# Rx_micro.net
KiCad netlist of a schematic drawn in Altium Designer
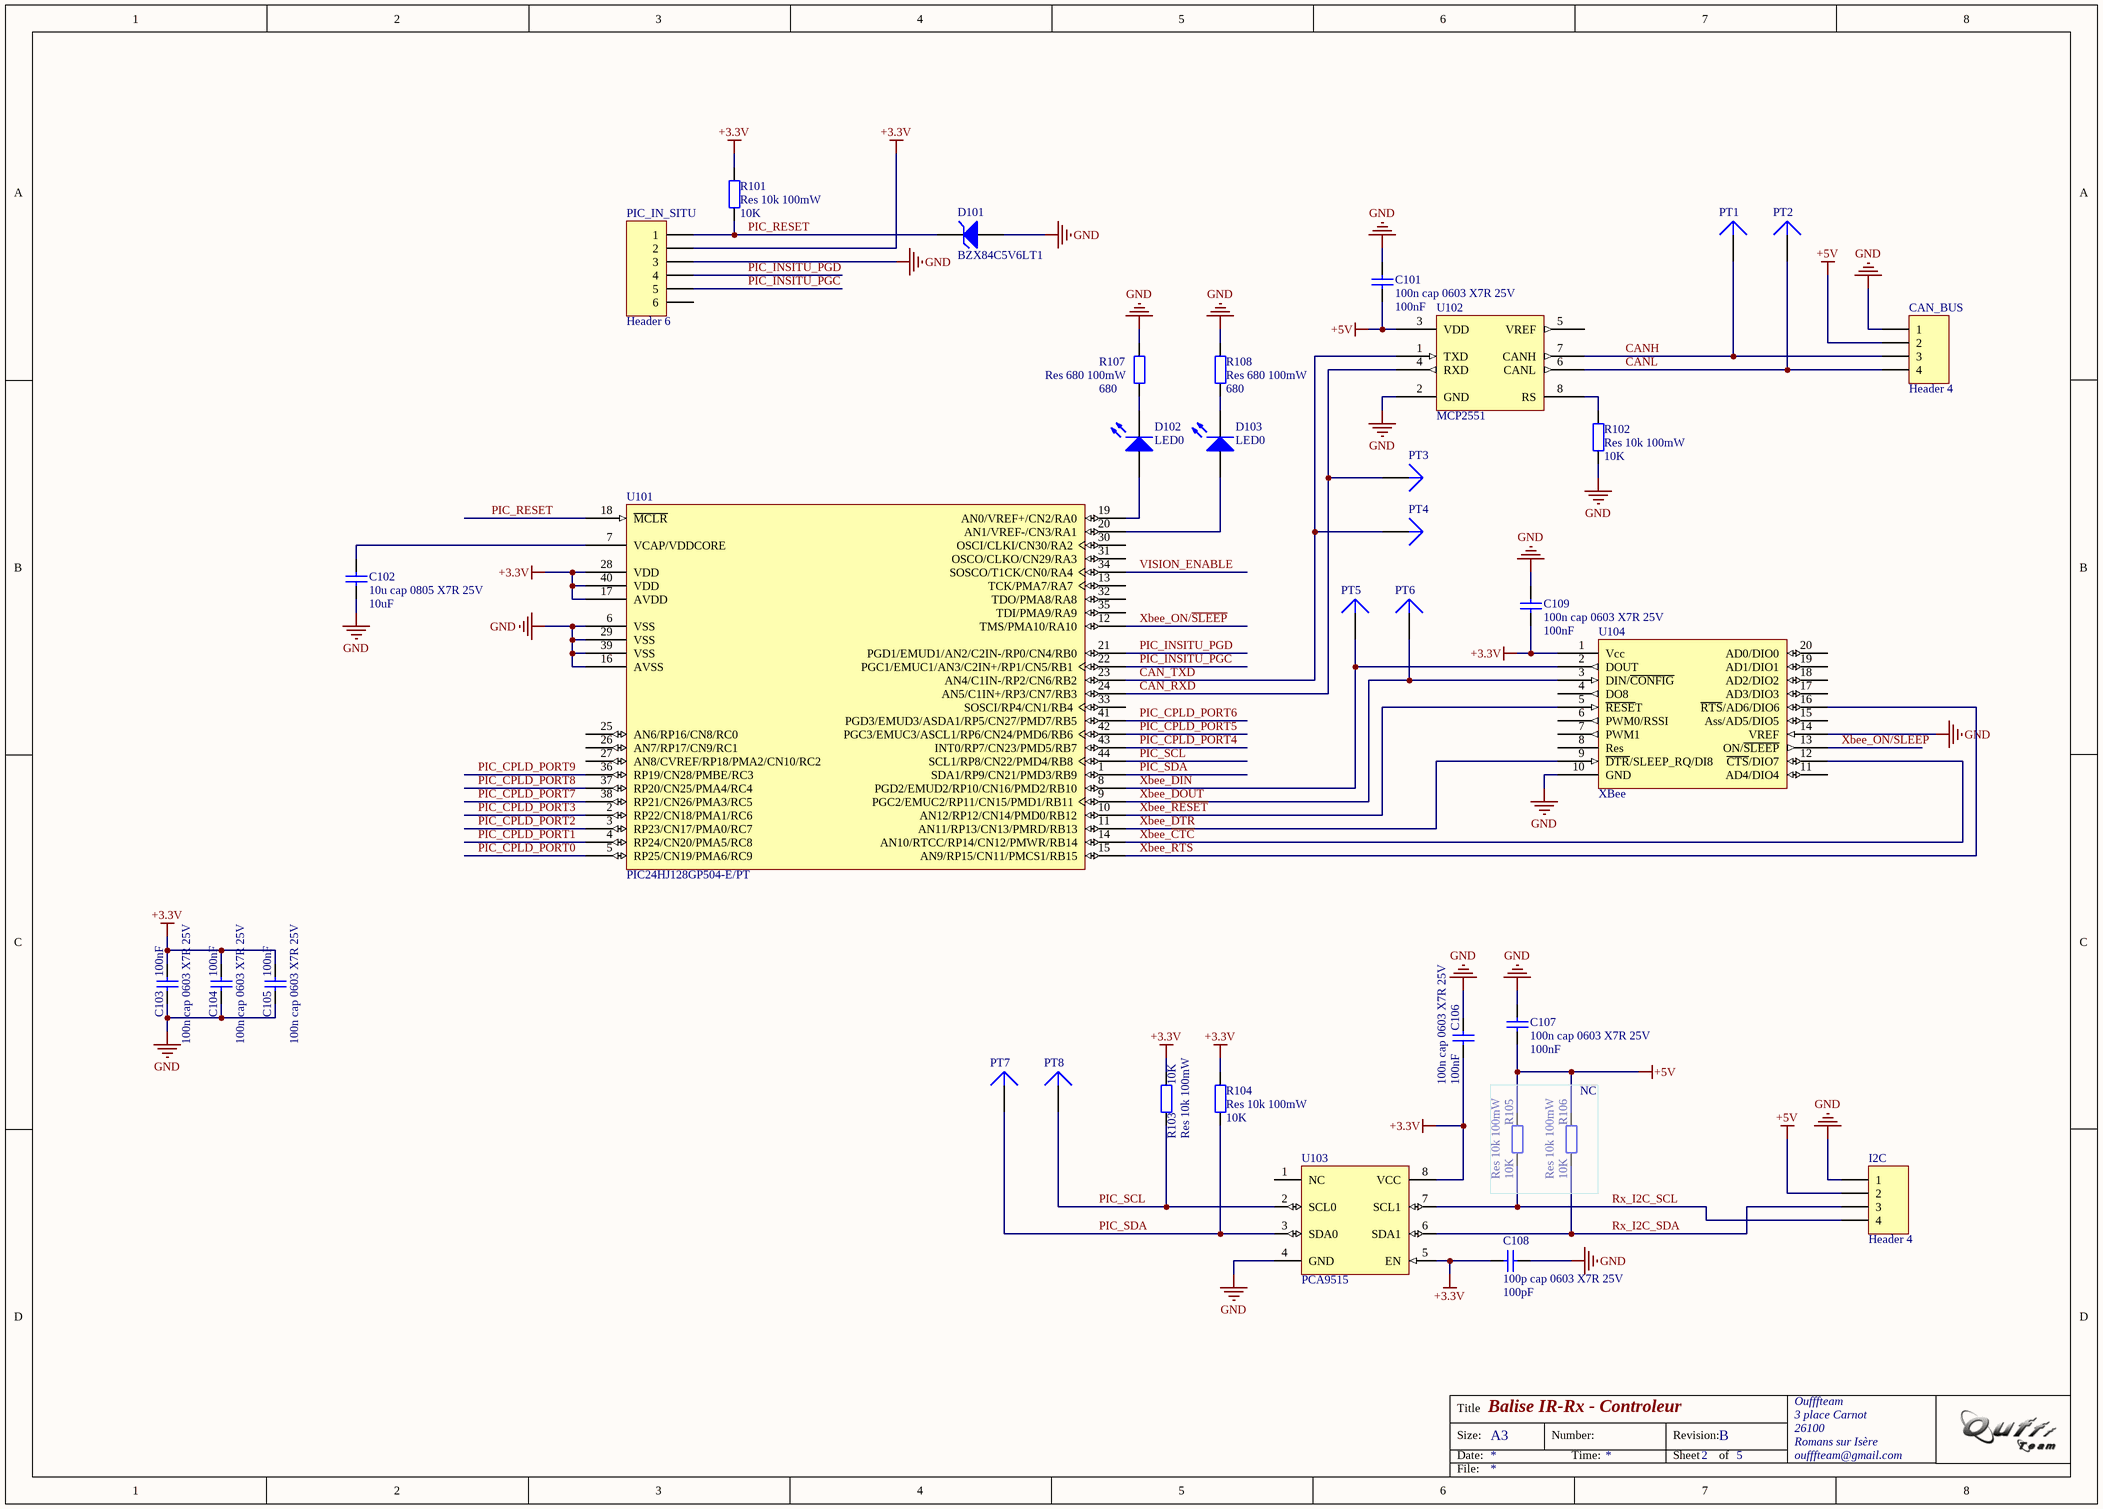
[diagram p0: Rx_micro.SchDoc]

(export (version "E")
  (design (tool "Eeschema 10.0.6"))
  (components
    (comp (ref "C101")
      (value "100n cap 0603 X7R 25V")
      (footprint "0603")
      (description "Capacitor")
      (fields (field (name "ALTIUM_VALUE") "100nF") (field (name "PUBLISHER") "Altium Limited"))
      (libsource (lib "Miscellaneous Devices") (part "Cap"))
    )
    (comp (ref "C102")
      (value "10u cap 0805 X7R 25V")
      (footprint "0805")
      (description "Capacitor")
      (fields (field (name "ALTIUM_VALUE") "10uF") (field (name "PUBLISHER") "Altium Limited"))
      (libsource (lib "Miscellaneous Devices") (part "Cap"))
    )
    (comp (ref "C103")
      (value "100n cap 0603 X7R 25V")
      (footprint "0603")
      (description "Capacitor")
      (fields (field (name "ALTIUM_VALUE") "100nF") (field (name "PUBLISHER") "Altium Limited"))
      (libsource (lib "Miscellaneous Devices") (part "Cap"))
    )
    (comp (ref "C104")
      (value "100n cap 0603 X7R 25V")
      (footprint "0603")
      (description "Capacitor")
      (fields (field (name "ALTIUM_VALUE") "100nF") (field (name "PUBLISHER") "Altium Limited"))
      (libsource (lib "Miscellaneous Devices") (part "Cap"))
    )
    (comp (ref "C105")
      (value "100n cap 0603 X7R 25V")
      (footprint "0603")
      (description "Capacitor")
      (fields (field (name "ALTIUM_VALUE") "100nF") (field (name "PUBLISHER") "Altium Limited"))
      (libsource (lib "Miscellaneous Devices") (part "Cap"))
    )
    (comp (ref "C106")
      (value "100n cap 0603 X7R 25V")
      (footprint "1608[0603]")
      (description "Capacitor")
      (fields (field (name "ALTIUM_VALUE") "100nF") (field (name "PUBLISHER") "Altium Limited"))
      (libsource (lib "Miscellaneous Devices") (part "Cap"))
    )
    (comp (ref "C107")
      (value "100n cap 0603 X7R 25V")
      (footprint "1608[0603]")
      (description "Capacitor")
      (fields (field (name "ALTIUM_VALUE") "100nF") (field (name "PUBLISHER") "Altium Limited"))
      (libsource (lib "Miscellaneous Devices") (part "Cap"))
    )
    (comp (ref "C108")
      (value "100p cap 0603 X7R 25V")
      (footprint "1608[0603]")
      (description "Capacitor")
      (fields (field (name "ALTIUM_VALUE") "100pF") (field (name "PUBLISHER") "Altium Limited"))
      (libsource (lib "Miscellaneous Devices") (part "Cap"))
    )
    (comp (ref "C109")
      (value "100n cap 0603 X7R 25V")
      (footprint "0603")
      (description "Capacitor")
      (fields (field (name "ALTIUM_VALUE") "100nF") (field (name "PUBLISHER") "Altium Limited"))
      (libsource (lib "Miscellaneous Devices") (part "Cap"))
    )
    (comp (ref "CAN_BUS")
      (value "Header 4")
      (footprint "HDR1X4")
      (description "Header, 4-Pin")
      (fields (field (name "PUBLISHER") "Altium Limited"))
      (libsource (lib "Miscellaneous Connectors") (part "Header 4"))
    )
    (comp (ref "D101")
      (value "BZX84C5V6LT1")
      (footprint "318-07")
      (description "Zener Voltage Regulator Diode")
      (fields (field (name "PUBLISHER") "Altium Limited"))
      (libsource (lib "Motorola Discrete Diode") (part "BZX84C5V6LT1"))
    )
    (comp (ref "D102")
      (value "LED0")
      (footprint "0603")
      (description "0603 Led")
      (fields (field (name "PUBLISHER") "Altium Limited"))
      (libsource (lib "Miscellaneous Devices") (part "LED0"))
    )
    (comp (ref "D103")
      (value "LED0")
      (footprint "0603")
      (description "0603 Led")
      (fields (field (name "PUBLISHER") "Altium Limited"))
      (libsource (lib "Miscellaneous Devices") (part "LED0"))
    )
    (comp (ref "I2C")
      (value "Header 4")
      (footprint "HDR1X4")
      (description "Header, 4-Pin")
      (fields (field (name "PUBLISHER") "Altium Limited"))
      (libsource (lib "Miscellaneous Connectors") (part "Header 4"))
    )
    (comp (ref "PIC_IN_SITU")
      (value "Header 6")
      (footprint "HDR1X6")
      (description "Header, 6-Pin")
      (fields (field (name "PUBLISHER") "Altium Limited"))
      (libsource (lib "Miscellaneous Connectors") (part "Header 6"))
    )
    (comp (ref "PT1")
      (value "Plug")
      (footprint "TP")
      (fields (field (name "PUBLISHER") "Altium Limited"))
      (libsource (lib "Miscellaneous Connectors") (part "Plug"))
    )
    (comp (ref "PT2")
      (value "Plug")
      (footprint "TP")
      (fields (field (name "PUBLISHER") "Altium Limited"))
      (libsource (lib "Miscellaneous Connectors") (part "Plug"))
    )
    (comp (ref "PT3")
      (value "Plug")
      (footprint "TP")
      (fields (field (name "PUBLISHER") "Altium Limited"))
      (libsource (lib "Miscellaneous Connectors") (part "Plug"))
    )
    (comp (ref "PT4")
      (value "Plug")
      (footprint "TP")
      (fields (field (name "PUBLISHER") "Altium Limited"))
      (libsource (lib "Miscellaneous Connectors") (part "Plug"))
    )
    (comp (ref "PT5")
      (value "Plug")
      (footprint "TP")
      (fields (field (name "PUBLISHER") "Altium Limited"))
      (libsource (lib "Miscellaneous Connectors") (part "Plug"))
    )
    (comp (ref "PT6")
      (value "Plug")
      (footprint "TP")
      (fields (field (name "PUBLISHER") "Altium Limited"))
      (libsource (lib "Miscellaneous Connectors") (part "Plug"))
    )
    (comp (ref "PT7")
      (value "Plug")
      (footprint "TP")
      (fields (field (name "PUBLISHER") "Altium Limited"))
      (libsource (lib "Miscellaneous Connectors") (part "Plug"))
    )
    (comp (ref "PT8")
      (value "Plug")
      (footprint "TP")
      (fields (field (name "PUBLISHER") "Altium Limited"))
      (libsource (lib "Miscellaneous Connectors") (part "Plug"))
    )
    (comp (ref "R101")
      (value "Res 10k 100mW")
      (footprint "0603")
      (description "Resistor")
      (fields (field (name "ALTIUM_VALUE") "10K") (field (name "PUBLISHER") "Altium Limited"))
      (libsource (lib "Miscellaneous Devices") (part "Res2"))
    )
    (comp (ref "R102")
      (value "Res 10k 100mW")
      (footprint "0603")
      (description "Resistor")
      (fields (field (name "ALTIUM_VALUE") "10K") (field (name "PUBLISHER") "Altium Limited"))
      (libsource (lib "Miscellaneous Devices") (part "Res2"))
    )
    (comp (ref "R103")
      (value "Res 10k 100mW")
      (footprint "0603")
      (description "Resistor")
      (fields (field (name "ALTIUM_VALUE") "10K") (field (name "PUBLISHER") "Altium Limited"))
      (libsource (lib "Miscellaneous Devices") (part "Res2"))
    )
    (comp (ref "R104")
      (value "Res 10k 100mW")
      (footprint "0603")
      (description "Resistor")
      (fields (field (name "ALTIUM_VALUE") "10K") (field (name "PUBLISHER") "Altium Limited"))
      (libsource (lib "Miscellaneous Devices") (part "Res2"))
    )
    (comp (ref "R105")
      (value "Res 10k 100mW")
      (footprint "1608[0603]")
      (description "Resistor")
      (fields (field (name "ALTIUM_VALUE") "10K") (field (name "PUBLISHER") "Altium Limited"))
      (libsource (lib "Miscellaneous Devices") (part "Res2"))
    )
    (comp (ref "R106")
      (value "Res 10k 100mW")
      (footprint "1608[0603]")
      (description "Resistor")
      (fields (field (name "ALTIUM_VALUE") "10K") (field (name "PUBLISHER") "Altium Limited"))
      (libsource (lib "Miscellaneous Devices") (part "Res2"))
    )
    (comp (ref "R107")
      (value "Res 680 100mW")
      (footprint "0603")
      (description "Resistor")
      (fields (field (name "ALTIUM_VALUE") "680") (field (name "PUBLISHER") "Altium Limited"))
      (libsource (lib "Miscellaneous Devices") (part "Res2"))
    )
    (comp (ref "R108")
      (value "Res 680 100mW")
      (footprint "0603")
      (description "Resistor")
      (fields (field (name "ALTIUM_VALUE") "680") (field (name "PUBLISHER") "Altium Limited"))
      (libsource (lib "Miscellaneous Devices") (part "Res2"))
    )
    (comp (ref "U101")
      (value "PIC24HJ128GP504-E/PT")
      (footprint "TQFP-PT44_N")
      (fields (field (name "PUBLISHER") "Altium Limited"))
      (libsource (lib "Microchip Microcontroller 16-Bit PIC24H") (part "PIC24HJ128GP504-E/PT"))
    )
    (comp (ref "U102")
      (value "MCP2551")
      (footprint "SOIC150-8_N")
      (description "High Speed Can Transceiver")
      (fields (field (name "PUBLISHER") "Altium Limited"))
      (libsource (lib "Microchip Interface Line Transceiver") (part "MCP2551"))
    )
    (comp (ref "U103")
      (value "PCA9515")
      (footprint "TSSOP-8")
      (description "DUAL BIDIRECTIONAL I2C BUS AND SMBus REPEATER")
      (libsource (lib "Oufff_Lib2") (part "PCA9515"))
    )
    (comp (ref "U104")
      (value "XBee")
      (footprint "XBee_SM")
      (description "OEM RF Modules")
      (libsource (lib "Oufff_Lib2") (part "XBee"))
    )
  )
  (nets
    (net (code "1") (name "+3.3V") (class "Default")
      (node (ref "C103") (pin "2") (pinfunction "2_2") (pintype "passive"))
      (node (ref "C104") (pin "2") (pinfunction "2_2") (pintype "passive"))
      (node (ref "C105") (pin "2") (pinfunction "2_2") (pintype "passive"))
      (node (ref "C106") (pin "1") (pinfunction "1_1") (pintype "passive"))
      (node (ref "C108") (pin "2") (pinfunction "2_2") (pintype "passive"))
      (node (ref "C109") (pin "1") (pinfunction "1_1") (pintype "passive"))
      (node (ref "PIC_IN_SITU") (pin "2") (pinfunction "2_2") (pintype "passive"))
      (node (ref "R101") (pin "2") (pinfunction "2_2") (pintype "passive"))
      (node (ref "R103") (pin "2") (pinfunction "2_2") (pintype "passive"))
      (node (ref "R104") (pin "2") (pinfunction "2_2") (pintype "passive"))
      (node (ref "U101") (pin "17") (pinfunction "AVDD_17") (pintype "power_in"))
      (node (ref "U101") (pin "28") (pinfunction "VDD_28") (pintype "power_in"))
      (node (ref "U101") (pin "40") (pinfunction "VDD_40") (pintype "power_in"))
      (node (ref "U103") (pin "5") (pinfunction "EN_5") (pintype "input"))
      (node (ref "U103") (pin "8") (pinfunction "VCC_8") (pintype "power_in"))
      (node (ref "U104") (pin "1") (pinfunction "Vcc_1") (pintype "power_in"))
    )
    (net (code "2") (name "+5V") (class "Default")
      (node (ref "C101") (pin "1") (pinfunction "1_1") (pintype "passive"))
      (node (ref "C107") (pin "2") (pinfunction "2_2") (pintype "passive"))
      (node (ref "CAN_BUS") (pin "2") (pinfunction "2_2") (pintype "passive"))
      (node (ref "I2C") (pin "2") (pinfunction "2_2") (pintype "passive"))
      (node (ref "R105") (pin "2") (pinfunction "2_2") (pintype "passive"))
      (node (ref "R106") (pin "2") (pinfunction "2_2") (pintype "passive"))
      (node (ref "U102") (pin "3") (pinfunction "VDD_3") (pintype "power_in"))
    )
    (net (code "3") (name "/CANH") (class "Default")
      (node (ref "CAN_BUS") (pin "3") (pinfunction "3_3") (pintype "passive"))
      (node (ref "PT1") (pin "1") (pinfunction "1_1") (pintype "passive"))
      (node (ref "U102") (pin "7") (pinfunction "CANH_7") (pintype "output"))
    )
    (net (code "4") (name "/CANL") (class "Default")
      (node (ref "CAN_BUS") (pin "4") (pinfunction "4_4") (pintype "passive"))
      (node (ref "PT2") (pin "1") (pinfunction "1_1") (pintype "passive"))
      (node (ref "U102") (pin "6") (pinfunction "CANL_6") (pintype "output"))
    )
    (net (code "5") (name "/CAN_RXD") (class "Default")
      (node (ref "PT3") (pin "1") (pinfunction "1_1") (pintype "passive"))
      (node (ref "U101") (pin "24") (pinfunction "AN5/C1IN+/RP3/CN7/RB3_24") (pintype "bidirectional"))
      (node (ref "U102") (pin "4") (pinfunction "RXD_4") (pintype "output"))
    )
    (net (code "6") (name "/CAN_TXD") (class "Default")
      (node (ref "PT4") (pin "1") (pinfunction "1_1") (pintype "passive"))
      (node (ref "U101") (pin "23") (pinfunction "AN4/C1IN-/RP2/CN6/RB2_23") (pintype "bidirectional"))
      (node (ref "U102") (pin "1") (pinfunction "TXD_1") (pintype "input"))
    )
    (net (code "7") (name "/PIC_CPLD_PORT0") (class "Default")
      (node (ref "U101") (pin "5") (pinfunction "RP25/CN19/PMA6/RC9_5") (pintype "bidirectional"))
    )
    (net (code "8") (name "/PIC_CPLD_PORT1") (class "Default")
      (node (ref "U101") (pin "4") (pinfunction "RP24/CN20/PMA5/RC8_4") (pintype "bidirectional"))
    )
    (net (code "9") (name "/PIC_CPLD_PORT2") (class "Default")
      (node (ref "U101") (pin "3") (pinfunction "RP23/CN17/PMA0/RC7_3") (pintype "bidirectional"))
    )
    (net (code "10") (name "/PIC_CPLD_PORT3") (class "Default")
      (node (ref "U101") (pin "2") (pinfunction "RP22/CN18/PMA1/RC6_2") (pintype "bidirectional"))
    )
    (net (code "11") (name "/PIC_CPLD_PORT4") (class "Default")
      (node (ref "U101") (pin "43") (pinfunction "INT0/RP7/CN23/PMD5/RB7_43") (pintype "bidirectional"))
    )
    (net (code "12") (name "/PIC_CPLD_PORT5") (class "Default")
      (node (ref "U101") (pin "42") (pinfunction "PGC3/EMUC3/ASCL1/RP6/CN24/PMD6/RB6_42") (pintype "bidirectional"))
    )
    (net (code "13") (name "/PIC_CPLD_PORT6") (class "Default")
      (node (ref "U101") (pin "41") (pinfunction "PGD3/EMUD3/ASDA1/RP5/CN27/PMD7/RB5_41") (pintype "bidirectional"))
    )
    (net (code "14") (name "/PIC_CPLD_PORT7") (class "Default")
      (node (ref "U101") (pin "38") (pinfunction "RP21/CN26/PMA3/RC5_38") (pintype "bidirectional"))
    )
    (net (code "15") (name "/PIC_CPLD_PORT8") (class "Default")
      (node (ref "U101") (pin "37") (pinfunction "RP20/CN25/PMA4/RC4_37") (pintype "bidirectional"))
    )
    (net (code "16") (name "/PIC_CPLD_PORT9") (class "Default")
      (node (ref "U101") (pin "36") (pinfunction "RP19/CN28/PMBE/RC3_36") (pintype "bidirectional"))
    )
    (net (code "17") (name "/PIC_INSITU_PGC") (class "Default")
      (node (ref "PIC_IN_SITU") (pin "5") (pinfunction "5_5") (pintype "passive"))
      (node (ref "U101") (pin "22") (pinfunction "PGC1/EMUC1/AN3/C2IN+/RP1/CN5/RB1_22") (pintype "bidirectional"))
    )
    (net (code "18") (name "/PIC_INSITU_PGD") (class "Default")
      (node (ref "PIC_IN_SITU") (pin "4") (pinfunction "4_4") (pintype "passive"))
      (node (ref "U101") (pin "21") (pinfunction "PGD1/EMUD1/AN2/C2IN-/RP0/CN4/RB0_21") (pintype "bidirectional"))
    )
    (net (code "19") (name "/PIC_RESET") (class "Default")
      (node (ref "D101") (pin "3") (pinfunction "K_3") (pintype "passive"))
      (node (ref "PIC_IN_SITU") (pin "1") (pinfunction "1_1") (pintype "passive"))
      (node (ref "R101") (pin "1") (pinfunction "1_1") (pintype "passive"))
      (node (ref "U101") (pin "18") (pinfunction "~{MCLR}_18") (pintype "input"))
    )
    (net (code "20") (name "/PIC_SCL") (class "Default")
      (node (ref "PT8") (pin "1") (pinfunction "1_1") (pintype "passive"))
      (node (ref "R103") (pin "1") (pinfunction "1_1") (pintype "passive"))
      (node (ref "U101") (pin "44") (pinfunction "SCL1/RP8/CN22/PMD4/RB8_44") (pintype "bidirectional"))
      (node (ref "U103") (pin "2") (pinfunction "SCL0_2") (pintype "bidirectional"))
    )
    (net (code "21") (name "/PIC_SDA") (class "Default")
      (node (ref "PT7") (pin "1") (pinfunction "1_1") (pintype "passive"))
      (node (ref "R104") (pin "1") (pinfunction "1_1") (pintype "passive"))
      (node (ref "U101") (pin "1") (pinfunction "SDA1/RP9/CN21/PMD3/RB9_1") (pintype "bidirectional"))
      (node (ref "U103") (pin "3") (pinfunction "SDA0_3") (pintype "bidirectional"))
    )
    (net (code "22") (name "/Rx_I2C_SCL") (class "Default")
      (node (ref "I2C") (pin "4") (pinfunction "4_4") (pintype "passive"))
      (node (ref "R105") (pin "1") (pinfunction "1_1") (pintype "passive"))
      (node (ref "U103") (pin "7") (pinfunction "SCL1_7") (pintype "bidirectional"))
    )
    (net (code "23") (name "/Rx_I2C_SDA") (class "Default")
      (node (ref "I2C") (pin "3") (pinfunction "3_3") (pintype "passive"))
      (node (ref "R106") (pin "1") (pinfunction "1_1") (pintype "passive"))
      (node (ref "U103") (pin "6") (pinfunction "SDA1_6") (pintype "bidirectional"))
    )
    (net (code "24") (name "/VISION_ENABLE") (class "Default")
      (node (ref "U101") (pin "34") (pinfunction "SOSCO/T1CK/CN0/RA4_34") (pintype "bidirectional"))
    )
    (net (code "25") (name "/Xbee_DIN") (class "Default")
      (node (ref "PT5") (pin "1") (pinfunction "1_1") (pintype "passive"))
      (node (ref "U101") (pin "8") (pinfunction "PGD2/EMUD2/RP10/CN16/PMD2/RB10_8") (pintype "bidirectional"))
      (node (ref "U104") (pin "2") (pinfunction "DOUT_2") (pintype "output"))
    )
    (net (code "26") (name "/Xbee_DOUT") (class "Default")
      (node (ref "PT6") (pin "1") (pinfunction "1_1") (pintype "passive"))
      (node (ref "U101") (pin "9") (pinfunction "PGC2/EMUC2/RP11/CN15/PMD1/RB11_9") (pintype "bidirectional"))
      (node (ref "U104") (pin "3") (pinfunction "DIN/~{CONFIG}_3") (pintype "input"))
    )
    (net (code "27") (name "/Xbee_DTR") (class "Default")
      (node (ref "U101") (pin "11") (pinfunction "AN11/RP13/CN13/PMRD/RB13_11") (pintype "bidirectional"))
      (node (ref "U104") (pin "9") (pinfunction "~{DTR}/SLEEP_RQ/DI8_9") (pintype "input"))
    )
    (net (code "28") (name "/Xbee_ON{slash}~{SLEEP}") (class "Default")
      (node (ref "U101") (pin "12") (pinfunction "TMS/PMA10/RA10_12") (pintype "bidirectional"))
      (node (ref "U104") (pin "13") (pinfunction "ON/~{SLEEP}_13") (pintype "output"))
    )
    (net (code "29") (name "/Xbee_~{CTC}") (class "Default")
      (node (ref "U101") (pin "14") (pinfunction "AN10/RTCC/RP14/CN12/PMWR/RB14_14") (pintype "bidirectional"))
      (node (ref "U104") (pin "12") (pinfunction "~{CTS}/DIO7_12") (pintype "bidirectional"))
    )
    (net (code "30") (name "/Xbee_~{RESET}") (class "Default")
      (node (ref "U101") (pin "10") (pinfunction "AN12/RP12/CN14/PMD0/RB12_10") (pintype "bidirectional"))
      (node (ref "U104") (pin "5") (pinfunction "~{RESE}T_5") (pintype "input"))
    )
    (net (code "31") (name "/Xbee_~{RTS}") (class "Default")
      (node (ref "U101") (pin "15") (pinfunction "AN9/RP15/CN11/PMCS1/RB15_15") (pintype "bidirectional"))
      (node (ref "U104") (pin "16") (pinfunction "~{RTS}/AD6/DIO6_16") (pintype "bidirectional"))
    )
    (net (code "32") (name "GND") (class "Default")
      (node (ref "C101") (pin "2") (pinfunction "2_2") (pintype "passive"))
      (node (ref "C102") (pin "1") (pinfunction "1_1") (pintype "passive"))
      (node (ref "C103") (pin "1") (pinfunction "1_1") (pintype "passive"))
      (node (ref "C104") (pin "1") (pinfunction "1_1") (pintype "passive"))
      (node (ref "C105") (pin "1") (pinfunction "1_1") (pintype "passive"))
      (node (ref "C106") (pin "2") (pinfunction "2_2") (pintype "passive"))
      (node (ref "C107") (pin "1") (pinfunction "1_1") (pintype "passive"))
      (node (ref "C108") (pin "1") (pinfunction "1_1") (pintype "passive"))
      (node (ref "C109") (pin "2") (pinfunction "2_2") (pintype "passive"))
      (node (ref "CAN_BUS") (pin "1") (pinfunction "1_1") (pintype "passive"))
      (node (ref "D101") (pin "1") (pinfunction "A_1") (pintype "passive"))
      (node (ref "I2C") (pin "1") (pinfunction "1_1") (pintype "passive"))
      (node (ref "PIC_IN_SITU") (pin "3") (pinfunction "3_3") (pintype "passive"))
      (node (ref "R102") (pin "1") (pinfunction "1_1") (pintype "passive"))
      (node (ref "R107") (pin "2") (pinfunction "2_2") (pintype "passive"))
      (node (ref "R108") (pin "2") (pinfunction "2_2") (pintype "passive"))
      (node (ref "U101") (pin "16") (pinfunction "AVSS_16") (pintype "power_in"))
      (node (ref "U101") (pin "29") (pinfunction "VSS_29") (pintype "power_in"))
      (node (ref "U101") (pin "39") (pinfunction "VSS_39") (pintype "power_in"))
      (node (ref "U101") (pin "6") (pinfunction "VSS_6") (pintype "power_in"))
      (node (ref "U102") (pin "2") (pinfunction "GND_2") (pintype "power_in"))
      (node (ref "U103") (pin "4") (pinfunction "GND_4") (pintype "power_in"))
      (node (ref "U104") (pin "10") (pinfunction "GND_10") (pintype "power_in"))
      (node (ref "U104") (pin "14") (pinfunction "VREF_14") (pintype "input"))
    )
    (net (code "33") (name "Net-(D102-A)") (class "Default")
      (node (ref "D102") (pin "1") (pinfunction "A_1") (pintype "passive"))
      (node (ref "U101") (pin "19") (pinfunction "AN0/VREF+/CN2/RA0_19") (pintype "bidirectional"))
    )
    (net (code "34") (name "Net-(D102-K)") (class "Default")
      (node (ref "D102") (pin "2") (pinfunction "K_2") (pintype "passive"))
      (node (ref "R107") (pin "1") (pinfunction "1_1") (pintype "passive"))
    )
    (net (code "35") (name "Net-(D103-A)") (class "Default")
      (node (ref "D103") (pin "1") (pinfunction "A_1") (pintype "passive"))
      (node (ref "U101") (pin "20") (pinfunction "AN1/VREF-/CN3/RA1_20") (pintype "bidirectional"))
    )
    (net (code "36") (name "Net-(D103-K)") (class "Default")
      (node (ref "D103") (pin "2") (pinfunction "K_2") (pintype "passive"))
      (node (ref "R108") (pin "1") (pinfunction "1_1") (pintype "passive"))
    )
    (net (code "37") (name "Net-(U101-VCAP{slash}VDDCORE)") (class "Default")
      (node (ref "C102") (pin "2") (pinfunction "2_2") (pintype "passive"))
      (node (ref "U101") (pin "7") (pinfunction "VCAP/VDDCORE_7") (pintype "power_in"))
    )
    (net (code "38") (name "Net-(U102-RS)") (class "Default")
      (node (ref "R102") (pin "2") (pinfunction "2_2") (pintype "passive"))
      (node (ref "U102") (pin "8") (pinfunction "RS_8") (pintype "passive"))
    )
    (net (code "39") (name "unconnected-(PIC_IN_SITU-Pad6)") (class "Default")
      (node (ref "PIC_IN_SITU") (pin "6") (pinfunction "6_6") (pintype "passive"))
    )
    (net (code "40") (name "unconnected-(U101-AN6{slash}RP16{slash}CN8{slash}RC0-Pad25)") (class "Default")
      (node (ref "U101") (pin "25") (pinfunction "AN6/RP16/CN8/RC0_25") (pintype "bidirectional"))
    )
    (net (code "41") (name "unconnected-(U101-AN7{slash}RP17{slash}CN9{slash}RC1-Pad26)") (class "Default")
      (node (ref "U101") (pin "26") (pinfunction "AN7/RP17/CN9/RC1_26") (pintype "bidirectional"))
    )
    (net (code "42") (name "unconnected-(U101-AN8{slash}CVREF{slash}RP18{slash}PMA2{slash}CN10{slash}RC2-Pad27)") (class "Default")
      (node (ref "U101") (pin "27") (pinfunction "AN8/CVREF/RP18/PMA2/CN10/RC2_27") (pintype "bidirectional"))
    )
    (net (code "43") (name "unconnected-(U101-OSCI{slash}CLKI{slash}CN30{slash}RA2-Pad30)") (class "Default")
      (node (ref "U101") (pin "30") (pinfunction "OSCI/CLKI/CN30/RA2_30") (pintype "bidirectional"))
    )
    (net (code "44") (name "unconnected-(U101-OSCO{slash}CLKO{slash}CN29{slash}RA3-Pad31)") (class "Default")
      (node (ref "U101") (pin "31") (pinfunction "OSCO/CLKO/CN29/RA3_31") (pintype "bidirectional"))
    )
    (net (code "45") (name "unconnected-(U101-SOSCI{slash}RP4{slash}CN1{slash}RB4-Pad33)") (class "Default")
      (node (ref "U101") (pin "33") (pinfunction "SOSCI/RP4/CN1/RB4_33") (pintype "bidirectional"))
    )
    (net (code "46") (name "unconnected-(U101-TCK{slash}PMA7{slash}RA7-Pad13)") (class "Default")
      (node (ref "U101") (pin "13") (pinfunction "TCK/PMA7/RA7_13") (pintype "bidirectional"))
    )
    (net (code "47") (name "unconnected-(U101-TDI{slash}PMA9{slash}RA9-Pad35)") (class "Default")
      (node (ref "U101") (pin "35") (pinfunction "TDI/PMA9/RA9_35") (pintype "bidirectional"))
    )
    (net (code "48") (name "unconnected-(U101-TDO{slash}PMA8{slash}RA8-Pad32)") (class "Default")
      (node (ref "U101") (pin "32") (pinfunction "TDO/PMA8/RA8_32") (pintype "bidirectional"))
    )
    (net (code "49") (name "unconnected-(U102-VREF-Pad5)") (class "Default")
      (node (ref "U102") (pin "5") (pinfunction "VREF_5") (pintype "output"))
    )
    (net (code "50") (name "unconnected-(U103-NC-Pad1)") (class "Default")
      (node (ref "U103") (pin "1") (pinfunction "NC_1") (pintype "passive"))
    )
    (net (code "51") (name "unconnected-(U104-AD0{slash}DIO0-Pad20)") (class "Default")
      (node (ref "U104") (pin "20") (pinfunction "AD0/DIO0_20") (pintype "bidirectional"))
    )
    (net (code "52") (name "unconnected-(U104-AD1{slash}DIO1-Pad19)") (class "Default")
      (node (ref "U104") (pin "19") (pinfunction "AD1/DIO1_19") (pintype "bidirectional"))
    )
    (net (code "53") (name "unconnected-(U104-AD2{slash}DIO2-Pad18)") (class "Default")
      (node (ref "U104") (pin "18") (pinfunction "AD2/DIO2_18") (pintype "bidirectional"))
    )
    (net (code "54") (name "unconnected-(U104-AD3{slash}DIO3-Pad17)") (class "Default")
      (node (ref "U104") (pin "17") (pinfunction "AD3/DIO3_17") (pintype "bidirectional"))
    )
    (net (code "55") (name "unconnected-(U104-AD4{slash}DIO4-Pad11)") (class "Default")
      (node (ref "U104") (pin "11") (pinfunction "AD4/DIO4_11") (pintype "bidirectional"))
    )
    (net (code "56") (name "unconnected-(U104-Ass{slash}AD5{slash}DIO5-Pad15)") (class "Default")
      (node (ref "U104") (pin "15") (pinfunction "Ass/AD5/DIO5_15") (pintype "bidirectional"))
    )
    (net (code "57") (name "unconnected-(U104-DO8-Pad4)") (class "Default")
      (node (ref "U104") (pin "4") (pinfunction "DO8_4") (pintype "output"))
    )
    (net (code "58") (name "unconnected-(U104-PWM0{slash}RSSI-Pad6)") (class "Default")
      (node (ref "U104") (pin "6") (pinfunction "PWM0/RSSI_6") (pintype "output"))
    )
    (net (code "59") (name "unconnected-(U104-PWM1-Pad7)") (class "Default")
      (node (ref "U104") (pin "7") (pinfunction "PWM1_7") (pintype "output"))
    )
    (net (code "60") (name "unconnected-(U104-Res-Pad8)") (class "Default")
      (node (ref "U104") (pin "8") (pinfunction "Res_8") (pintype "passive"))
    )
  )
)
